# nRF24L01_Proto_Board.net
KiCad netlist of a schematic drawn in EAGLE
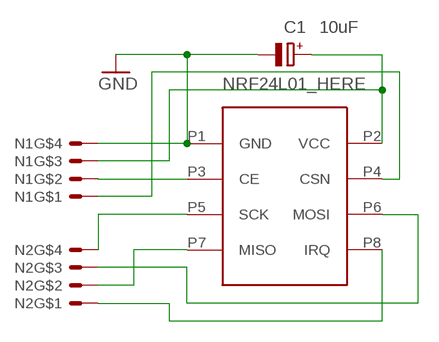
[diagram p0: schematic, sheet 1]

(export (version "E")
  (design (tool "Eeschema 10.0.6"))
  (components
    (comp (ref "C1")
      (value "10uF")
      (footprint "eagle-import:E2,5-6")
      (libsource (lib "eagle-import") (part "CPOL-EUE2.5-6"))
    )
    (comp (ref "N1")
      (value "4PINHEADER_S")
      (footprint "eagle-import:4PINHEADER_S")
      (libsource (lib "eagle-import") (part "4PINHEADER_S"))
    )
    (comp (ref "N2")
      (value "4PINHEADER_S")
      (footprint "eagle-import:4PINHEADER_S")
      (libsource (lib "eagle-import") (part "4PINHEADER_S"))
    )
    (comp (ref "NRF24L01_HERE")
      (value "NRF24L01A")
      (footprint "eagle-import:NRF24L01")
      (libsource (lib "eagle-import") (part "NRF24L01A"))
    )
  )
  (nets
    (net (code "1") (name "GND") (class "Default")
      (node (ref "C1") (pin "-") (pinfunction "-_-") (pintype "passive"))
      (node (ref "N1") (pin "N3") (pinfunction "S_N3") (pintype "passive"))
      (node (ref "NRF24L01_HERE") (pin "P1") (pinfunction "GND_P1") (pintype "input"))
    )
    (net (code "2") (name "Net-(N1A-S)") (class "Default")
      (node (ref "N1") (pin "N0") (pinfunction "S_N0") (pintype "passive"))
      (node (ref "NRF24L01_HERE") (pin "P4") (pinfunction "CSN_P4") (pintype "bidirectional"))
    )
    (net (code "3") (name "Net-(N1B-S)") (class "Default")
      (node (ref "N1") (pin "N1") (pinfunction "S_N1") (pintype "passive"))
      (node (ref "NRF24L01_HERE") (pin "P3") (pinfunction "CE_P3") (pintype "bidirectional"))
    )
    (net (code "4") (name "Net-(N1C-S)") (class "Default")
      (node (ref "C1") (pin "+") (pinfunction "+_+") (pintype "passive"))
      (node (ref "N1") (pin "N2") (pinfunction "S_N2") (pintype "passive"))
      (node (ref "NRF24L01_HERE") (pin "P2") (pinfunction "VCC_P2") (pintype "power_in"))
    )
    (net (code "5") (name "Net-(N2A-S)") (class "Default")
      (node (ref "N2") (pin "N0") (pinfunction "S_N0") (pintype "passive"))
      (node (ref "NRF24L01_HERE") (pin "P8") (pinfunction "IRQ_P8") (pintype "bidirectional"))
    )
    (net (code "6") (name "Net-(N2B-S)") (class "Default")
      (node (ref "N2") (pin "N1") (pinfunction "S_N1") (pintype "passive"))
      (node (ref "NRF24L01_HERE") (pin "P7") (pinfunction "MISO_P7") (pintype "bidirectional"))
    )
    (net (code "7") (name "Net-(N2C-S)") (class "Default")
      (node (ref "N2") (pin "N2") (pinfunction "S_N2") (pintype "passive"))
      (node (ref "NRF24L01_HERE") (pin "P6") (pinfunction "MOSI_P6") (pintype "bidirectional"))
    )
    (net (code "8") (name "Net-(N2D-S)") (class "Default")
      (node (ref "N2") (pin "N3") (pinfunction "S_N3") (pintype "passive"))
      (node (ref "NRF24L01_HERE") (pin "P5") (pinfunction "SCK_P5") (pintype "bidirectional"))
    )
  )
)
